# Power.net
KiCad netlist of a schematic drawn in Altium Designer
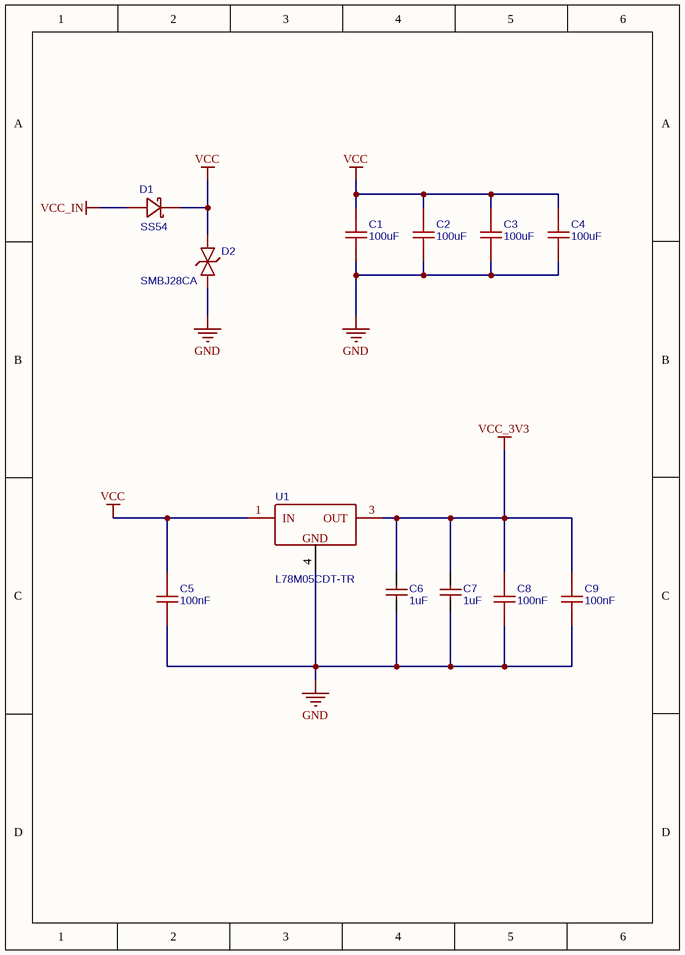
[diagram p0: Power.SchDoc]

(export (version "E")
  (design (tool "Eeschema 10.0.6"))
  (components
    (comp (ref "C1")
      (value "100uF")
      (footprint "C1206")
      (fields
        (field (name "BOM_SUPPLIER PART") "C312983")
        (field (name "BOM_MANUFACTURER PART") "GRM31CR61A107ME05L")
        (field (name "CONTRIBUTOR") "LCSC")
      )
      (libsource (lib "100uF") (part "100uF"))
    )
    (comp (ref "C2")
      (value "100uF")
      (footprint "C1206")
      (fields
        (field (name "BOM_SUPPLIER PART") "C312983")
        (field (name "BOM_MANUFACTURER PART") "GRM31CR61A107ME05L")
        (field (name "CONTRIBUTOR") "LCSC")
      )
      (libsource (lib "100uF") (part "100uF"))
    )
    (comp (ref "C3")
      (value "100uF")
      (footprint "C1206")
      (fields
        (field (name "BOM_SUPPLIER PART") "C312983")
        (field (name "BOM_MANUFACTURER PART") "GRM31CR61A107ME05L")
        (field (name "CONTRIBUTOR") "LCSC")
      )
      (libsource (lib "100uF") (part "100uF"))
    )
    (comp (ref "C4")
      (value "100uF")
      (footprint "C1206")
      (fields
        (field (name "BOM_SUPPLIER PART") "C312983")
        (field (name "BOM_MANUFACTURER PART") "GRM31CR61A107ME05L")
        (field (name "CONTRIBUTOR") "LCSC")
      )
      (libsource (lib "100uF") (part "100uF"))
    )
    (comp (ref "C5")
      (value "100nF")
      (footprint "C0603")
      (fields
        (field (name "BOM_MANUFACTURER PART") "CL10B104KB8NNNC")
        (field (name "BOM_SUPPLIER PART") "C1591")
      )
      (libsource (lib "0.1uF") (part "100nF"))
    )
    (comp (ref "C6")
      (value "1uF")
      (footprint "C0603")
      (fields
        (field (name "BOM_MANUFACTURER PART") "CL10A105KB8NNNC")
        (field (name "BOM_SUPPLIER PART") "C15849")
      )
      (libsource (lib "1uF") (part "1uF"))
    )
    (comp (ref "C7")
      (value "1uF")
      (footprint "C0603")
      (fields
        (field (name "BOM_MANUFACTURER PART") "CL10A105KB8NNNC")
        (field (name "BOM_SUPPLIER PART") "C15849")
      )
      (libsource (lib "1uF") (part "1uF"))
    )
    (comp (ref "C8")
      (value "100nF")
      (footprint "C0603")
      (fields
        (field (name "BOM_MANUFACTURER PART") "CL10B104KB8NNNC")
        (field (name "BOM_SUPPLIER PART") "C1591")
      )
      (libsource (lib "0.1uF") (part "100nF"))
    )
    (comp (ref "C9")
      (value "100nF")
      (footprint "C0603")
      (fields
        (field (name "BOM_MANUFACTURER PART") "CL10B104KB8NNNC")
        (field (name "BOM_SUPPLIER PART") "C1591")
      )
      (libsource (lib "0.1uF") (part "100nF"))
    )
    (comp (ref "D1")
      (value "SS54")
      (footprint "SMA_L4.3-W2.6-LS5.0-RD")
      (fields (field (name "BOM_SUPPLIER PART") "C727065") (field (name "CONTRIBUTOR") "LCSC"))
      (libsource (lib "SS54") (part "SS54_C727065"))
    )
    (comp (ref "D2")
      (value "SMBJ28CA")
      (footprint "SMB_L4.6-W3.6-LS5.3-BI")
      (fields (field (name "BOM_SUPPLIER PART") "C908204") (field (name "CONTRIBUTOR") "LCSC"))
      (libsource (lib "SMBJ28CA") (part "SMBJ28CA_C908204"))
    )
    (comp (ref "U1")
      (value "L78M05CDT-TR")
      (footprint "TO-252-2_L6.5-W6.1-P4.58-LS10.0-TL")
      (fields (field (name "BOM_SUPPLIER PART") "C55509"))
      (libsource (lib "L78M05CDT-TR") (part "L78M05CDT-TR"))
    )
  )
  (nets
    (net (code "1") (name "GND") (class "Default")
      (node (ref "C1") (pin "2") (pinfunction "2_2") (pintype "passive"))
      (node (ref "C2") (pin "2") (pinfunction "2_2") (pintype "passive"))
      (node (ref "C3") (pin "2") (pinfunction "2_2") (pintype "passive"))
      (node (ref "C4") (pin "2") (pinfunction "2_2") (pintype "passive"))
      (node (ref "C5") (pin "1") (pinfunction "1_1") (pintype "passive"))
      (node (ref "C6") (pin "1") (pinfunction "1_1") (pintype "passive"))
      (node (ref "C7") (pin "1") (pinfunction "1_1") (pintype "passive"))
      (node (ref "C8") (pin "1") (pinfunction "1_1") (pintype "passive"))
      (node (ref "C9") (pin "1") (pinfunction "1_1") (pintype "passive"))
      (node (ref "D2") (pin "1") (pinfunction "1_1") (pintype "passive"))
      (node (ref "U1") (pin "4") (pinfunction "GND_4") (pintype "passive"))
    )
    (net (code "2") (name "VCC") (class "Default")
      (node (ref "C1") (pin "1") (pinfunction "1_1") (pintype "passive"))
      (node (ref "C2") (pin "1") (pinfunction "1_1") (pintype "passive"))
      (node (ref "C3") (pin "1") (pinfunction "1_1") (pintype "passive"))
      (node (ref "C4") (pin "1") (pinfunction "1_1") (pintype "passive"))
      (node (ref "C5") (pin "2") (pinfunction "2_2") (pintype "passive"))
      (node (ref "D1") (pin "1") (pinfunction "1_1") (pintype "passive"))
      (node (ref "D2") (pin "2") (pinfunction "2_2") (pintype "passive"))
      (node (ref "U1") (pin "1") (pinfunction "IN_1") (pintype "passive"))
    )
    (net (code "3") (name "VCC_3V3") (class "Default")
      (node (ref "C6") (pin "2") (pinfunction "2_2") (pintype "passive"))
      (node (ref "C7") (pin "2") (pinfunction "2_2") (pintype "passive"))
      (node (ref "C8") (pin "2") (pinfunction "2_2") (pintype "passive"))
      (node (ref "C9") (pin "2") (pinfunction "2_2") (pintype "passive"))
      (node (ref "U1") (pin "3") (pinfunction "OUT_3") (pintype "passive"))
    )
    (net (code "4") (name "VCC_IN") (class "Default")
      (node (ref "D1") (pin "2") (pinfunction "2_2") (pintype "passive"))
    )
  )
)
